# Voltage_Supervisor.net
KiCad netlist of a schematic drawn in Altium Designer
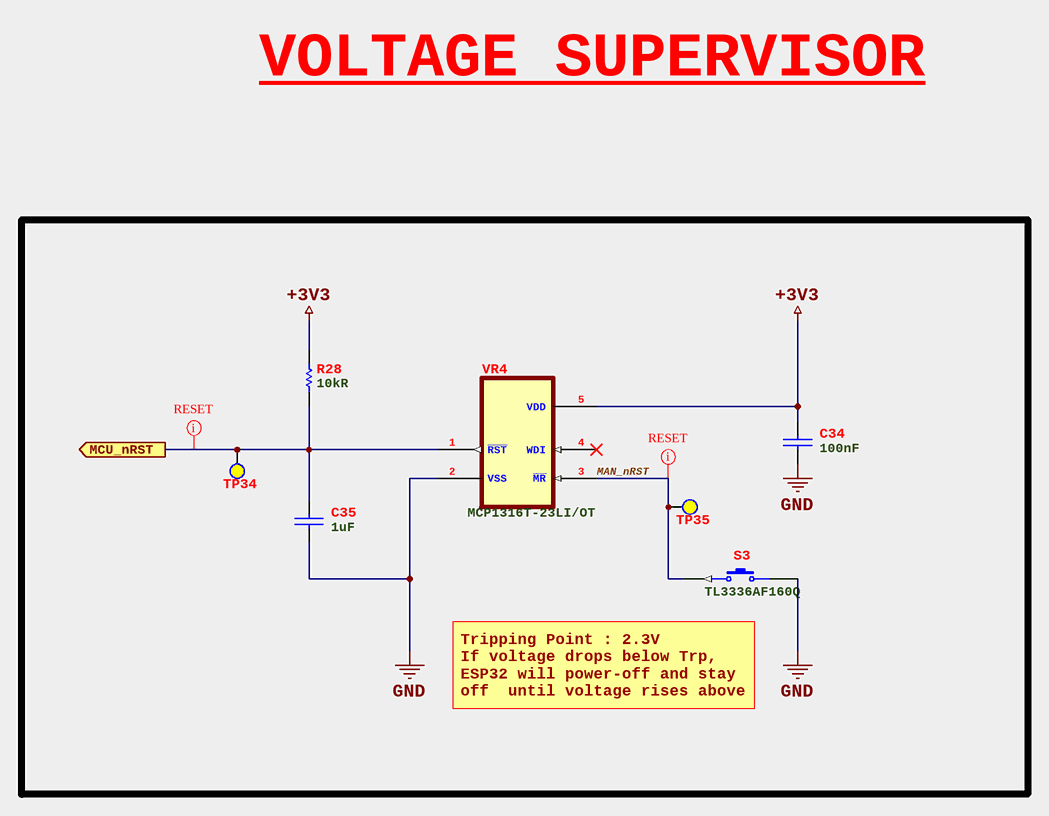
[diagram p0: Voltage Supervisor.SchDoc]

(export (version "E")
  (design (tool "Eeschema 10.0.6"))
  (components
    (comp (ref "C34")
      (value "100nF")
      (footprint "CAP_0603")
      (description "0.1 µF ±10% 50V Ceramic Capacitor X7R 0603 (1608 Metric)")
      (fields
        (field (name "MANUFACTURER") "Yageo")
        (field (name "MANUFACTURER PART NUMBER") "CC0603KRX7R9BB104")
      )
      (libsource (lib "Cellar Watchdog") (part "CAP_0.1uF-50V-10%_0603"))
    )
    (comp (ref "C35")
      (value "1uF")
      (footprint "CAP_0805")
      (description "1 µF ±10% 16V Ceramic Capacitor X7R 0603 (1608 Metric)")
      (fields
        (field (name "MANUFACTURER") "Yageo")
        (field (name "MANUFACTURER PART NUMBER") "CC0603KRX7R7BB105")
      )
      (libsource (lib "Cellar Watchdog") (part "CAP_1uF-16V-10%_0603"))
    )
    (comp (ref "R28")
      (value "10kR")
      (footprint "RES_0603")
      (description "10 kOhms ±1% 0.1W, 1/10W Chip Resistor 0603 (1608 Metric) Moisture Resistant Thick Film")
      (fields
        (field (name "MANUFACTURER") "Yageo")
        (field (name "MANUFACTURER PART NUMBER") "RC0603FR-0710KL")
      )
      (libsource (lib "Cellar Watchdog") (part "RES_10kR-100mW-1%_0603"))
    )
    (comp (ref "S3")
      (value "TL3336AF160Q")
      (footprint "SW-TACTILE-SPST_TL3336")
      (description "Tactile Switch SPST-NO Side Actuated Surface Mount, Right Angle")
      (fields (field (name "MANUFACTURER") "E-Switch"))
      (libsource (lib "Cellar Watchdog") (part "SW2-NO-SPST_TL3336AF160Q_SMD"))
    )
    (comp (ref "TP34")
      (value "MCU_nRST")
      (footprint "TEST POINT HOLE")
      (description "PCB Test Point")
      (libsource (lib "Cellar Watchdog") (part "Test Point"))
    )
    (comp (ref "TP35")
      (value "MAN_nRST")
      (footprint "TEST POINT HOLE")
      (description "PCB Test Point")
      (libsource (lib "Cellar Watchdog") (part "Test Point"))
    )
    (comp (ref "VR4")
      (value "MCP1316T-23LI/OT")
      (footprint "REG_SOT95P280X145-5N")
      (description "Supervisor Push-Pull, Totem Pole 1 Channel SOT-23-5")
      (fields (field (name "MANUFACTURER") "Microchip"))
      (libsource (lib "Cellar Watchdog") (part "SUP_2.3V-ActiveLow-140ms_SOT23-5"))
    )
  )
  (nets
    (net (code "1") (name "+3V3") (class "Default")
      (node (ref "C34") (pin "1") (pinfunction "1_1") (pintype "passive"))
      (node (ref "R28") (pin "2") (pinfunction "2_2") (pintype "passive"))
      (node (ref "VR4") (pin "5") (pinfunction "VDD_5") (pintype "power_in"))
    )
    (net (code "2") (name "/MAN_nRST") (class "Default")
      (node (ref "S3") (pin "1") (pinfunction "1_1") (pintype "output"))
      (node (ref "TP35") (pin "TP") (pinfunction "TP_TP") (pintype "passive"))
      (node (ref "VR4") (pin "3") (pinfunction "MR_3") (pintype "input"))
    )
    (net (code "3") (name "/MCU_nRST") (class "Default")
      (node (ref "C35") (pin "1") (pinfunction "1_1") (pintype "passive"))
      (node (ref "R28") (pin "1") (pinfunction "1_1") (pintype "passive"))
      (node (ref "TP34") (pin "TP") (pinfunction "TP_TP") (pintype "passive"))
      (node (ref "VR4") (pin "1") (pinfunction "RST_1") (pintype "output"))
    )
    (net (code "4") (name "GND") (class "Default")
      (node (ref "C34") (pin "2") (pinfunction "2_2") (pintype "passive"))
      (node (ref "C35") (pin "2") (pinfunction "2_2") (pintype "passive"))
      (node (ref "S3") (pin "2") (pinfunction "2_2") (pintype "power_in"))
      (node (ref "VR4") (pin "2") (pinfunction "VSS_2") (pintype "power_in"))
    )
    (net (code "5") (name "unconnected-(VR4-WDI-Pad4)") (class "Default")
      (node (ref "VR4") (pin "4") (pinfunction "WDI_4") (pintype "input+no_connect"))
    )
  )
)
